# SCH_555-Chaser_2025-10-31.net
KiCad netlist of a schematic drawn in EasyEDA
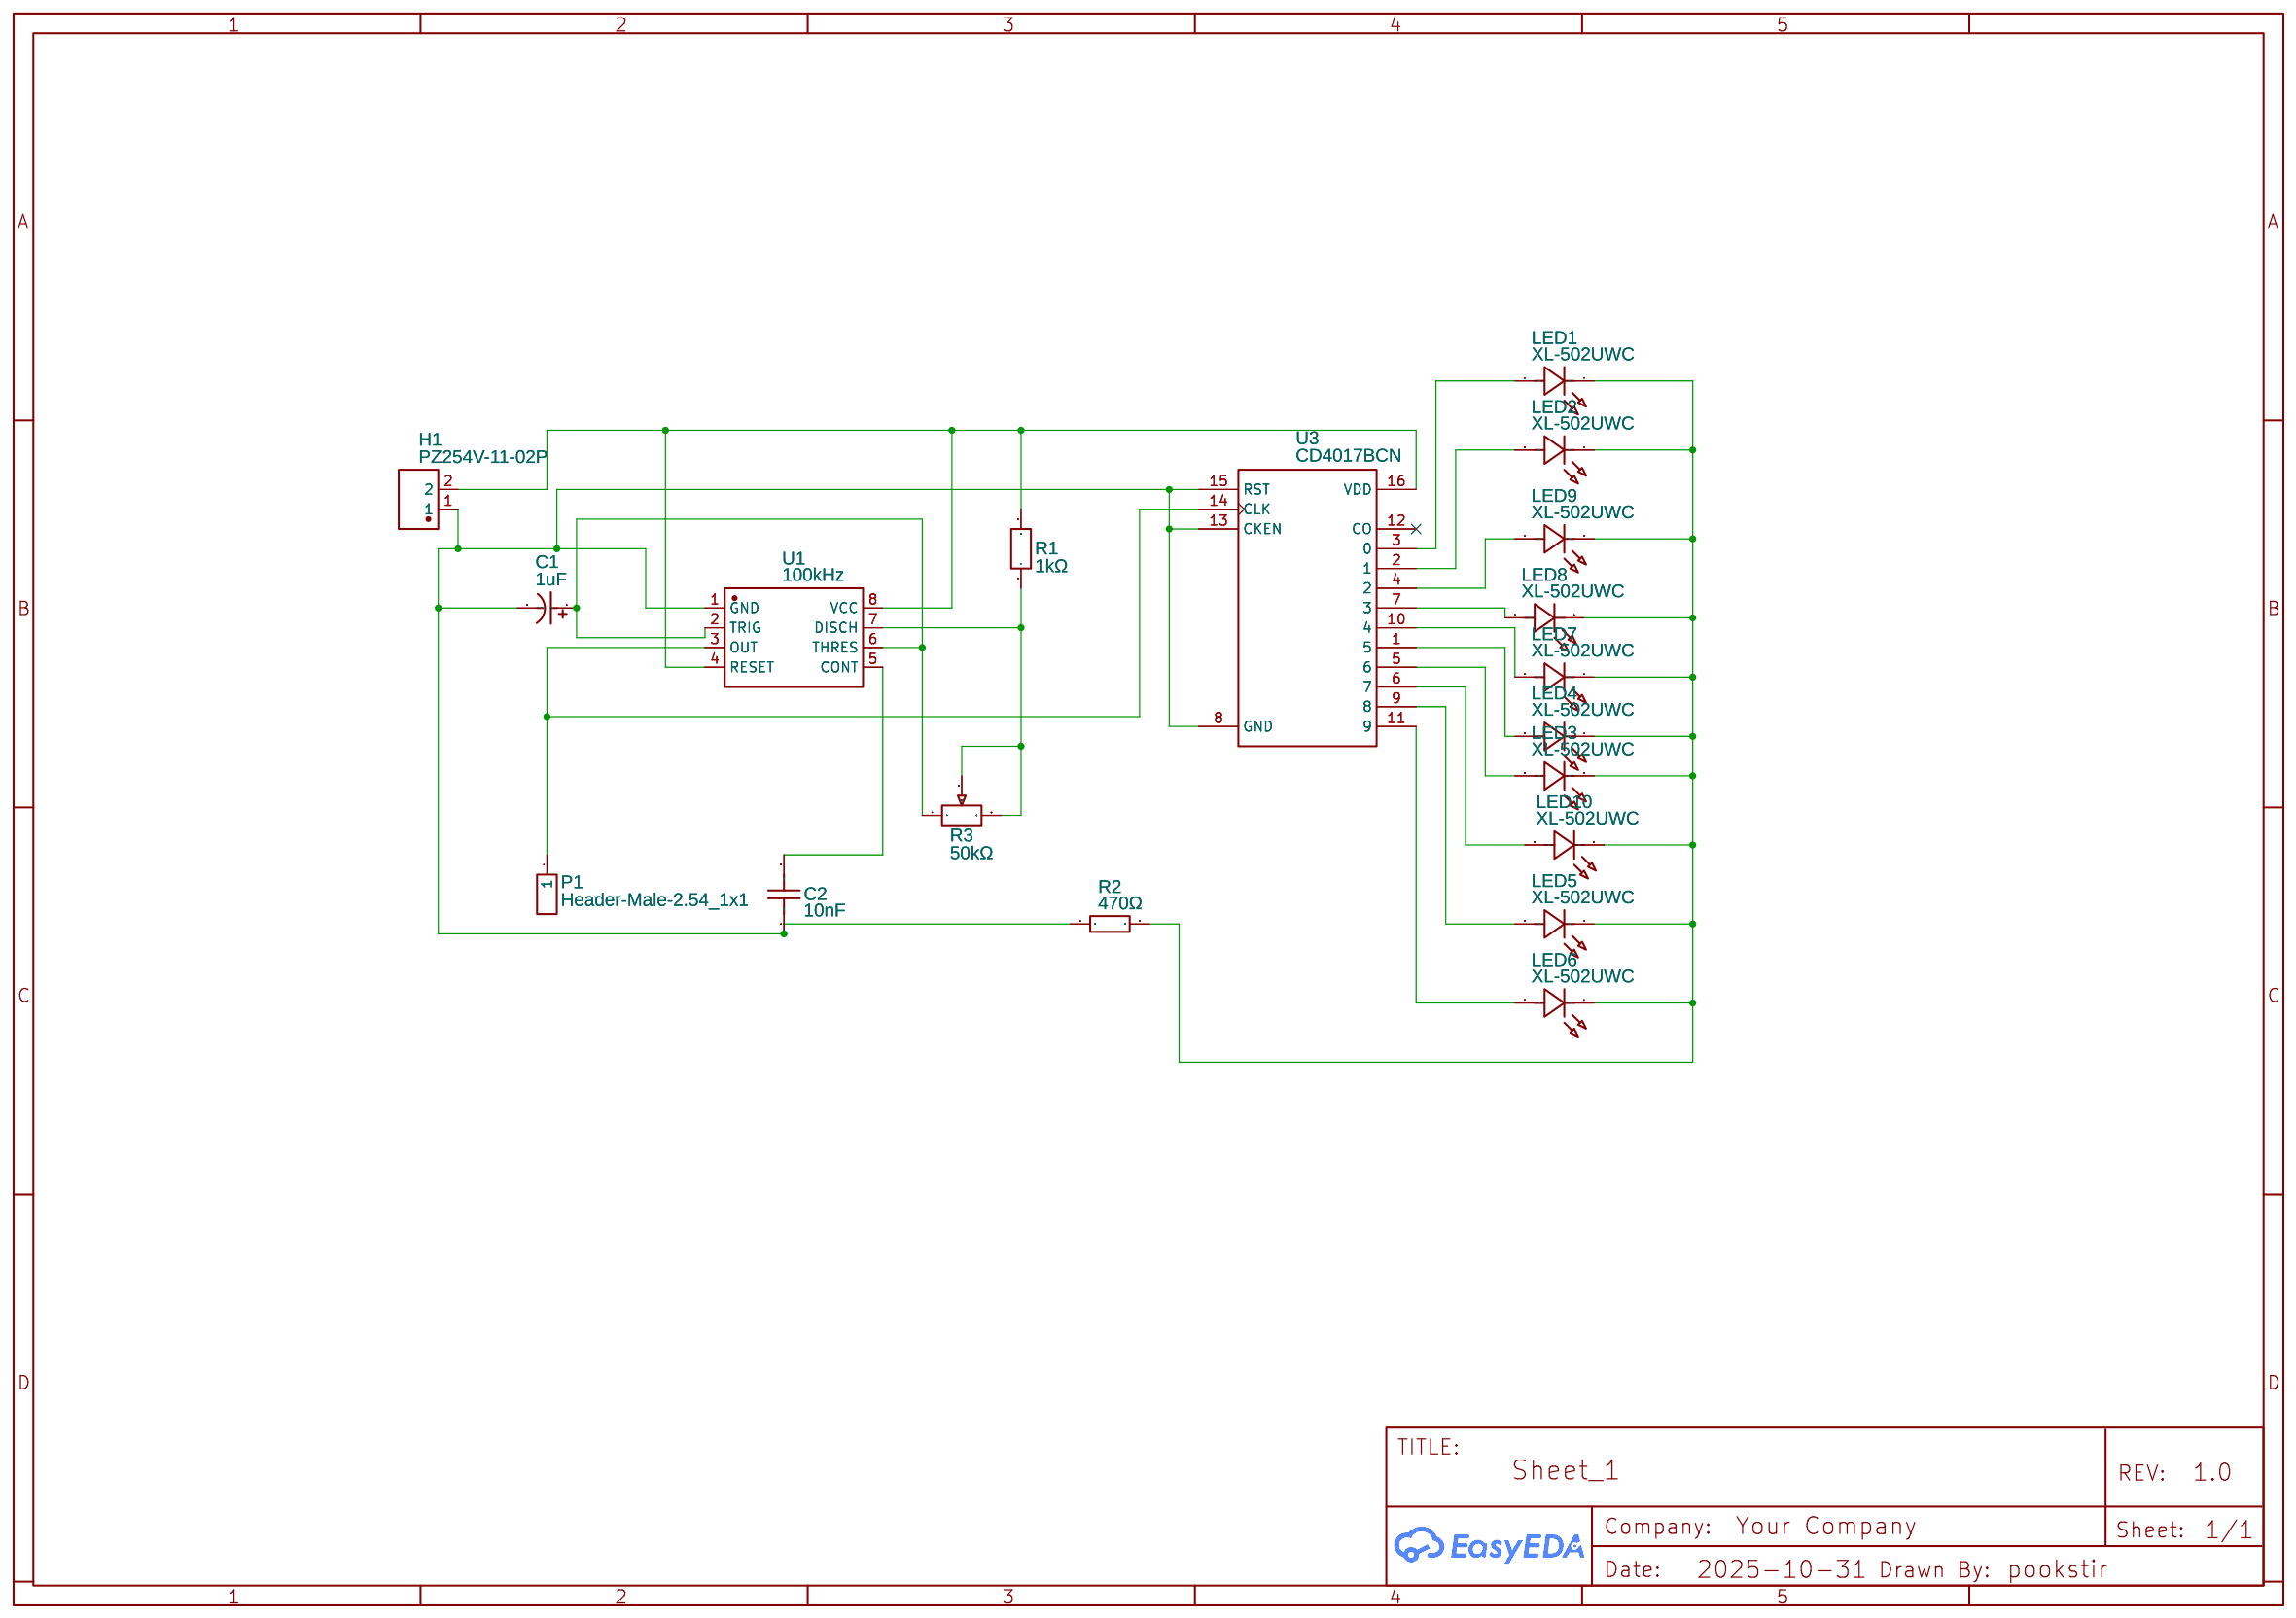
[diagram p0: schematic sheet]

(export (version "E")
  (design (tool "Eeschema 10.0.6"))
  (components
    (comp (ref "C1")
      (value "1uF")
      (fields (field (name "Manufacturer Part") "KF010M050C110A") (field (name "Manufacturer") "CapXon(丰宾)"))
      (libsource (lib "") (part "KF010M050C110A"))
    )
    (comp (ref "C2")
      (value "10nF")
      (fields (field (name "Manufacturer Part") "N09F1B103MN0B0S0N0") (field (name "Manufacturer") "STE(松田)"))
      (libsource (lib "") (part "N09F1B103MN0B0S0N0"))
    )
    (comp (ref "H1")
      (value "PZ254V-11-02P")
      (fields (field (name "Manufacturer") "XFCN(兴飞)"))
      (libsource (lib "") (part "PZ254V-11-02P"))
    )
    (comp (ref "LED1")
      (value "XL-502UWC")
      (fields (field (name "Manufacturer") "XINGLIGHT(成兴光)"))
      (libsource (lib "") (part "XL-502UWC"))
    )
    (comp (ref "LED2")
      (value "XL-502UWC")
      (fields (field (name "Manufacturer") "XINGLIGHT(成兴光)"))
      (libsource (lib "") (part "XL-502UWC"))
    )
    (comp (ref "LED3")
      (value "XL-502UWC")
      (fields (field (name "Manufacturer") "XINGLIGHT(成兴光)"))
      (libsource (lib "") (part "XL-502UWC"))
    )
    (comp (ref "LED4")
      (value "XL-502UWC")
      (fields (field (name "Manufacturer") "XINGLIGHT(成兴光)"))
      (libsource (lib "") (part "XL-502UWC"))
    )
    (comp (ref "LED5")
      (value "XL-502UWC")
      (fields (field (name "Manufacturer") "XINGLIGHT(成兴光)"))
      (libsource (lib "") (part "XL-502UWC"))
    )
    (comp (ref "LED6")
      (value "XL-502UWC")
      (fields (field (name "Manufacturer") "XINGLIGHT(成兴光)"))
      (libsource (lib "") (part "XL-502UWC"))
    )
    (comp (ref "LED7")
      (value "XL-502UWC")
      (fields (field (name "Manufacturer") "XINGLIGHT(成兴光)"))
      (libsource (lib "") (part "XL-502UWC"))
    )
    (comp (ref "LED8")
      (value "XL-502UWC")
      (fields (field (name "Manufacturer") "XINGLIGHT(成兴光)"))
      (libsource (lib "") (part "XL-502UWC"))
    )
    (comp (ref "LED9")
      (value "XL-502UWC")
      (fields (field (name "Manufacturer") "XINGLIGHT(成兴光)"))
      (libsource (lib "") (part "XL-502UWC"))
    )
    (comp (ref "LED10")
      (value "XL-502UWC")
      (fields (field (name "Manufacturer") "XINGLIGHT(成兴光)"))
      (libsource (lib "") (part "XL-502UWC"))
    )
    (comp (ref "P1")
      (value "Header-Male-2.54_1x1")
      (fields (field (name "Manufacturer Part") "2.54-1*1P针") (field (name "Manufacturer") "BOOMELE(博穆精密)"))
      (libsource (lib "") (part "Header-Male-2.54_1x1"))
    )
    (comp (ref "R1")
      (value "1kΩ")
      (fields (field (name "Manufacturer Part") "MF1/4W-1KΩ±1%T52") (field (name "Manufacturer") "华星机电"))
      (libsource (lib "") (part "MF1/4W-1KΩ±1%T52"))
    )
    (comp (ref "R2")
      (value "470Ω")
      (fields
        (field (name "Manufacturer Part") "MFR0W4F4700A50")
        (field (name "Manufacturer") "UNI-ROYAL(厚声)")
      )
      (libsource (lib "") (part "MFR0W4F4700A50"))
    )
    (comp (ref "R3")
      (value "50kΩ")
      (fields (field (name "Manufacturer Part") "3296X-1-503") (field (name "Manufacturer") "BOCHEN(博晨)"))
      (libsource (lib "") (part "3296X-1-503_C118912"))
    )
    (comp (ref "U1")
      (value "100kHz")
      (fields (field (name "Manufacturer Part") "NE555P") (field (name "Manufacturer") "TI(德州仪器)"))
      (libsource (lib "") (part "NE555P"))
    )
    (comp (ref "U3") (value "CD4017BCN") (libsource (lib "") (part "CD4017BCN")))
  )
  (nets
    (net (code "1") (name "Net-(LED1-A)") (class "Default")
      (node (ref "LED1") (pin "2") (pinfunction "A_2") (pintype "unspecified"))
      (node (ref "U3") (pin "3") (pinfunction "0_3") (pintype "output"))
    )
    (net (code "2") (name "Net-(LED1-K)") (class "Default")
      (node (ref "LED1") (pin "1") (pinfunction "K_1") (pintype "unspecified"))
      (node (ref "LED10") (pin "1") (pinfunction "K_1") (pintype "unspecified"))
      (node (ref "LED2") (pin "1") (pinfunction "K_1") (pintype "unspecified"))
      (node (ref "LED3") (pin "1") (pinfunction "K_1") (pintype "unspecified"))
      (node (ref "LED4") (pin "1") (pinfunction "K_1") (pintype "unspecified"))
      (node (ref "LED5") (pin "1") (pinfunction "K_1") (pintype "unspecified"))
      (node (ref "LED6") (pin "1") (pinfunction "K_1") (pintype "unspecified"))
      (node (ref "LED7") (pin "1") (pinfunction "K_1") (pintype "unspecified"))
      (node (ref "LED8") (pin "1") (pinfunction "K_1") (pintype "unspecified"))
      (node (ref "LED9") (pin "1") (pinfunction "K_1") (pintype "unspecified"))
      (node (ref "R2") (pin "2") (pinfunction "2_2") (pintype "input"))
    )
    (net (code "3") (name "Net-(LED2-A)") (class "Default")
      (node (ref "LED2") (pin "2") (pinfunction "A_2") (pintype "unspecified"))
      (node (ref "U3") (pin "2") (pinfunction "1_2") (pintype "output"))
    )
    (net (code "4") (name "Net-(LED3-A)") (class "Default")
      (node (ref "LED3") (pin "2") (pinfunction "A_2") (pintype "unspecified"))
      (node (ref "U3") (pin "5") (pinfunction "6_5") (pintype "output"))
    )
    (net (code "5") (name "Net-(LED4-A)") (class "Default")
      (node (ref "LED4") (pin "2") (pinfunction "A_2") (pintype "unspecified"))
      (node (ref "U3") (pin "1") (pinfunction "5_1") (pintype "output"))
    )
    (net (code "6") (name "Net-(LED5-A)") (class "Default")
      (node (ref "LED5") (pin "2") (pinfunction "A_2") (pintype "unspecified"))
      (node (ref "U3") (pin "9") (pinfunction "8_9") (pintype "output"))
    )
    (net (code "7") (name "Net-(LED6-A)") (class "Default")
      (node (ref "LED6") (pin "2") (pinfunction "A_2") (pintype "unspecified"))
      (node (ref "U3") (pin "11") (pinfunction "9_11") (pintype "output"))
    )
    (net (code "8") (name "Net-(LED7-A)") (class "Default")
      (node (ref "LED7") (pin "2") (pinfunction "A_2") (pintype "unspecified"))
      (node (ref "U3") (pin "10") (pinfunction "4_10") (pintype "output"))
    )
    (net (code "9") (name "Net-(LED8-A)") (class "Default")
      (node (ref "LED8") (pin "2") (pinfunction "A_2") (pintype "unspecified"))
      (node (ref "U3") (pin "7") (pinfunction "3_7") (pintype "output"))
    )
    (net (code "10") (name "Net-(LED9-A)") (class "Default")
      (node (ref "LED9") (pin "2") (pinfunction "A_2") (pintype "unspecified"))
      (node (ref "U3") (pin "4") (pinfunction "2_4") (pintype "output"))
    )
    (net (code "11") (name "Net-(LED10-A)") (class "Default")
      (node (ref "LED10") (pin "2") (pinfunction "A_2") (pintype "unspecified"))
      (node (ref "U3") (pin "6") (pinfunction "7_6") (pintype "output"))
    )
    (net (code "12") (name "Net-(U1-CONT)") (class "Default")
      (node (ref "C2") (pin "2") (pinfunction "2_2") (pintype "unspecified"))
      (node (ref "U1") (pin "5") (pinfunction "CONT_5") (pintype "unspecified"))
    )
    (net (code "13") (name "Net-(U1-DISCH)") (class "Default")
      (node (ref "R1") (pin "1") (pinfunction "1_1") (pintype "unspecified"))
      (node (ref "R3") (pin "2") (pinfunction "2_2") (pintype "input"))
      (node (ref "R3") (pin "3") (pinfunction "3_3") (pintype "input"))
      (node (ref "U1") (pin "7") (pinfunction "DISCH_7") (pintype "unspecified"))
    )
    (net (code "14") (name "Net-(U1-GND)") (class "Default")
      (node (ref "C1") (pin "2") (pinfunction "2_2") (pintype "input"))
      (node (ref "C2") (pin "1") (pinfunction "1_1") (pintype "unspecified"))
      (node (ref "H1") (pin "1") (pinfunction "1_1") (pintype "unspecified"))
      (node (ref "R2") (pin "1") (pinfunction "1_1") (pintype "input"))
      (node (ref "U1") (pin "1") (pinfunction "GND_1") (pintype "unspecified"))
      (node (ref "U3") (pin "13") (pinfunction "CKEN_13") (pintype "unspecified"))
      (node (ref "U3") (pin "15") (pinfunction "RST_15") (pintype "unspecified"))
      (node (ref "U3") (pin "8") (pinfunction "GND_8") (pintype "passive"))
    )
    (net (code "15") (name "Net-(U1-OUT)") (class "Default")
      (node (ref "P1") (pin "1") (pinfunction "1_1") (pintype "input"))
      (node (ref "U1") (pin "3") (pinfunction "OUT_3") (pintype "unspecified"))
      (node (ref "U3") (pin "14") (pinfunction "CLK_14") (pintype "unspecified"))
    )
    (net (code "16") (name "Net-(U1-RESET)") (class "Default")
      (node (ref "H1") (pin "2") (pinfunction "2_2") (pintype "unspecified"))
      (node (ref "R1") (pin "2") (pinfunction "2_2") (pintype "unspecified"))
      (node (ref "U1") (pin "4") (pinfunction "RESET_4") (pintype "unspecified"))
      (node (ref "U1") (pin "8") (pinfunction "VCC_8") (pintype "unspecified"))
      (node (ref "U3") (pin "16") (pinfunction "VDD_16") (pintype "passive"))
    )
    (net (code "17") (name "Net-(U1-THRES)") (class "Default")
      (node (ref "C1") (pin "1") (pinfunction "1_1") (pintype "input"))
      (node (ref "R3") (pin "1") (pinfunction "1_1") (pintype "input"))
      (node (ref "U1") (pin "2") (pinfunction "TRIG_2") (pintype "unspecified"))
      (node (ref "U1") (pin "6") (pinfunction "THRES_6") (pintype "unspecified"))
    )
    (net (code "18") (name "unconnected-(U3-CO-Pad12)") (class "Default")
      (node (ref "U3") (pin "12") (pinfunction "CO_12") (pintype "output+no_connect"))
    )
  )
)
